# design.net
KiCad netlist of a schematic drawn in EasyEDA
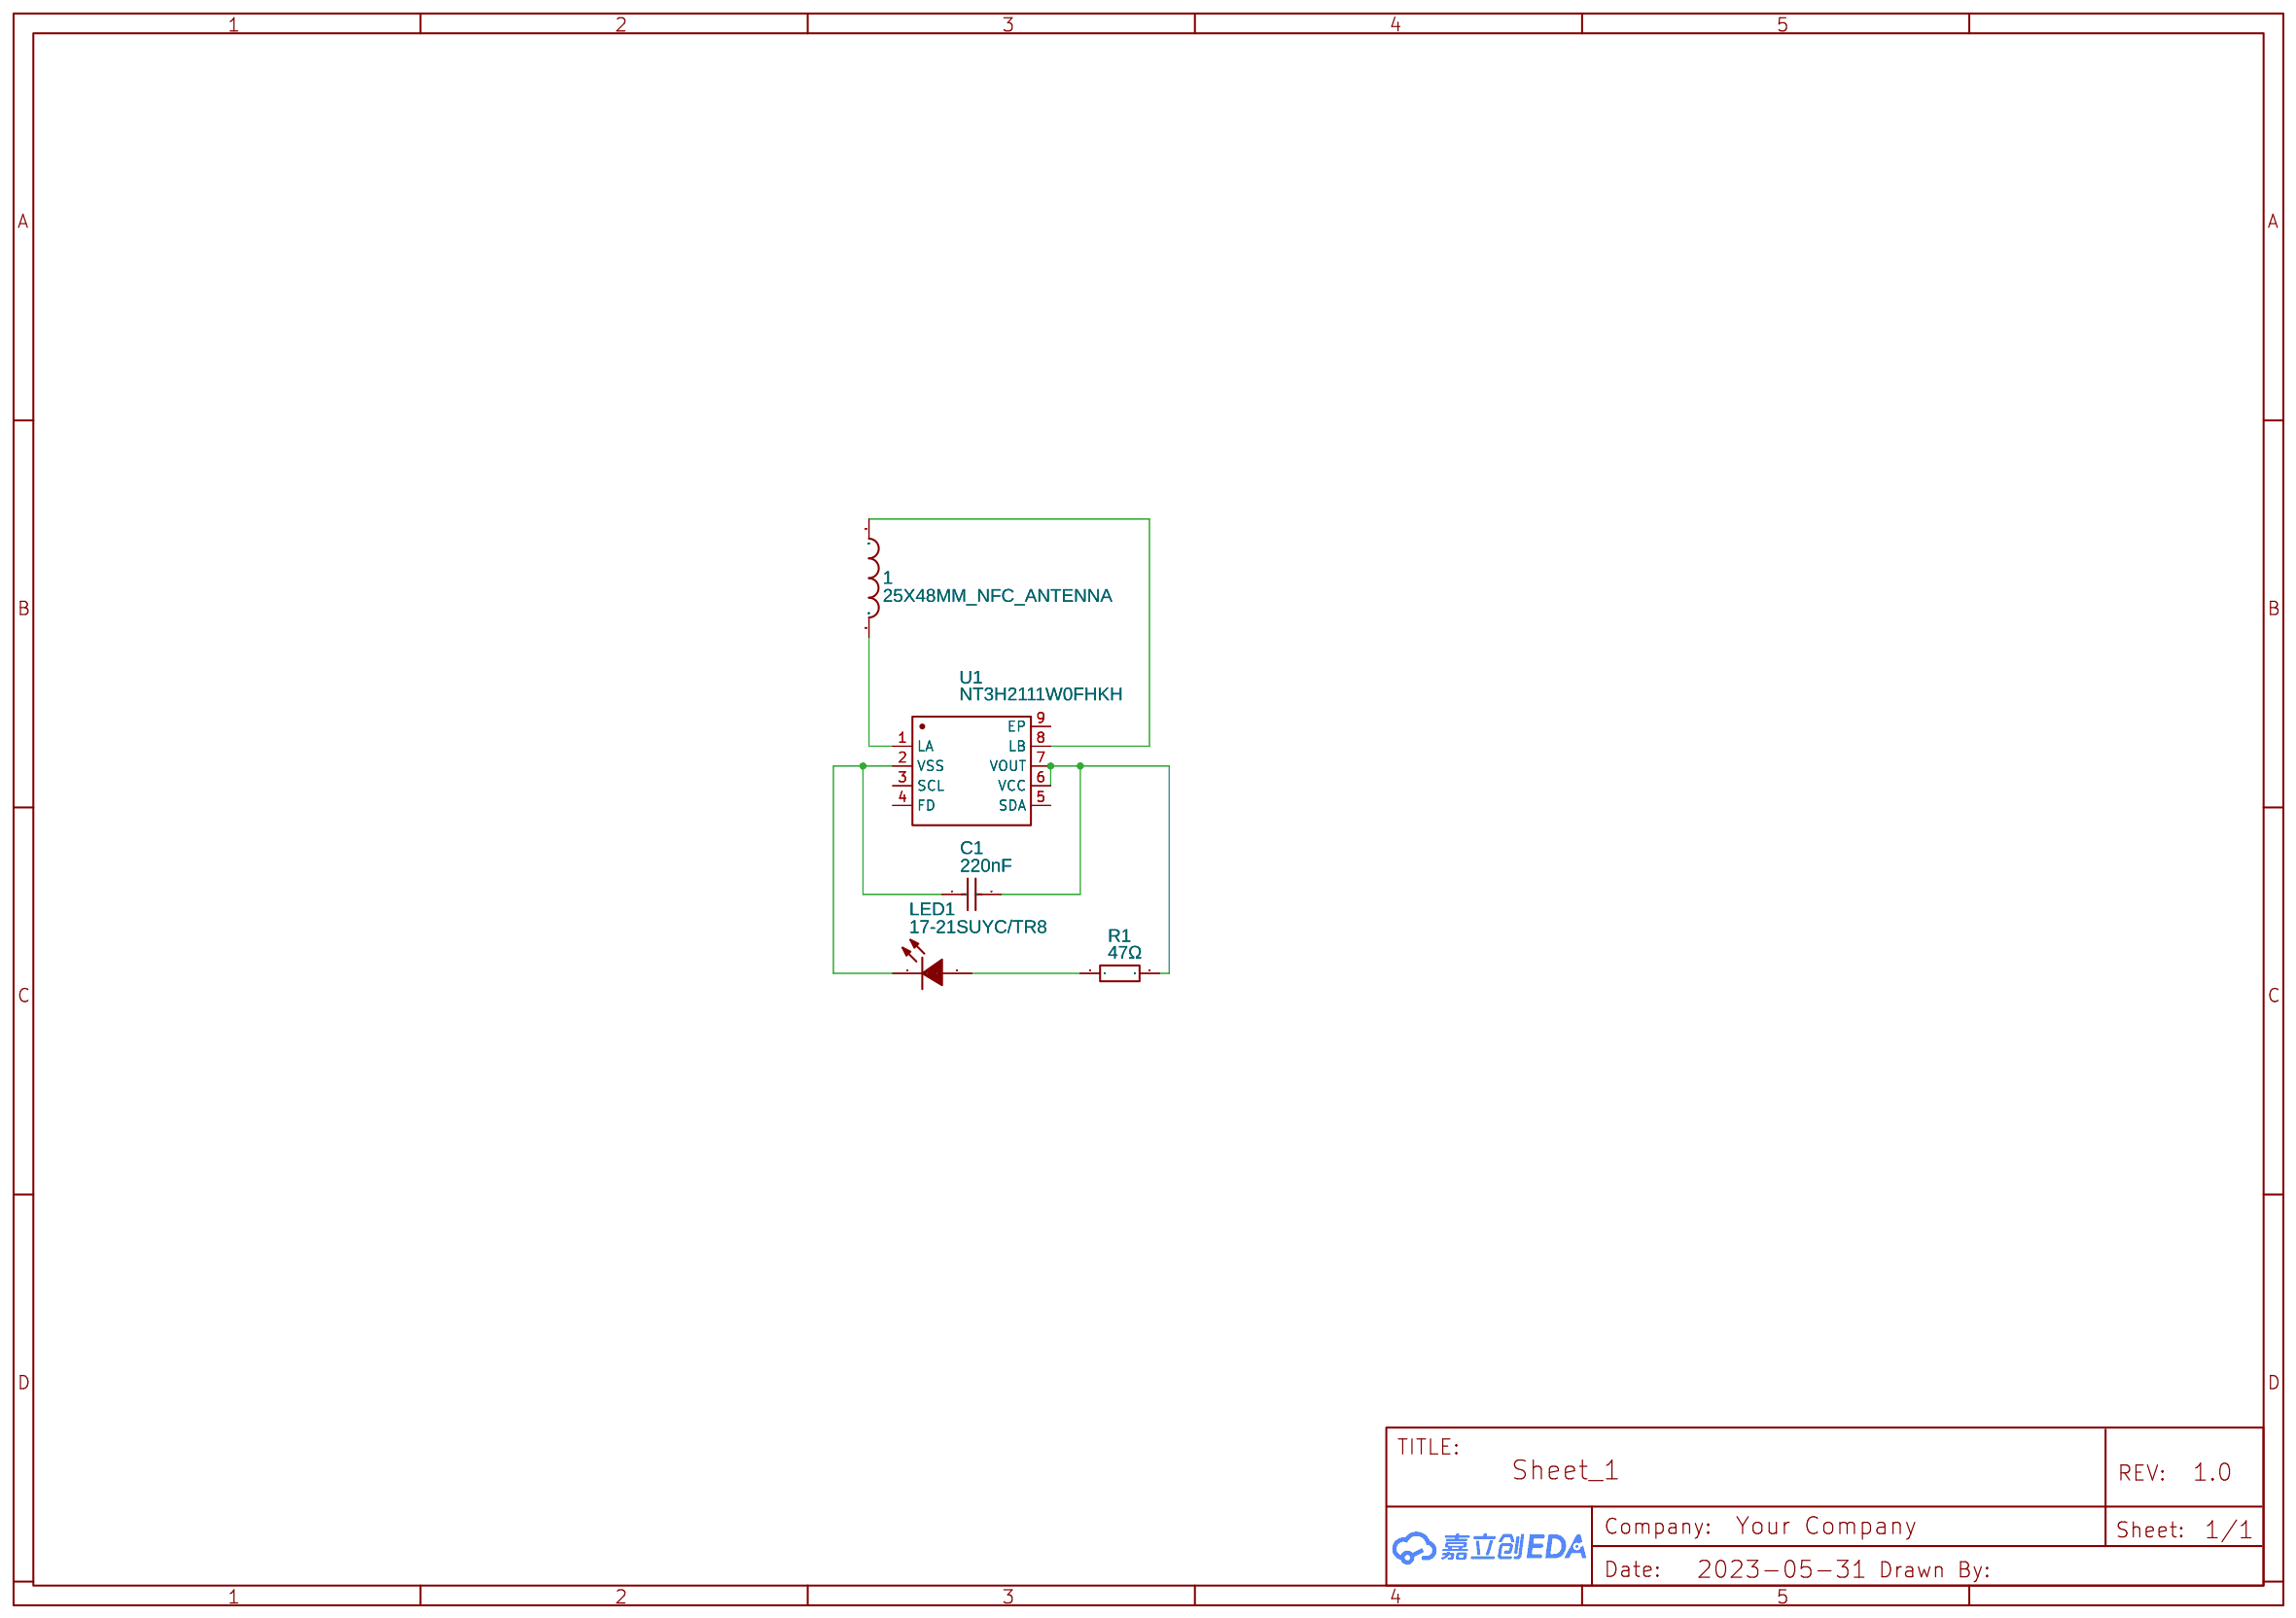
[diagram p0: schematic sheet]

(export (version "E")
  (design (tool "Eeschema 10.0.6"))
  (components
    (comp (ref "1") (value "25X48MM_NFC_ANTENNA") (libsource (lib "") (part "25X48MM_NFC_ANTENNA")))
    (comp (ref "C1")
      (value "220nF")
      (fields
        (field (name "BOM_Manufacturer Part") "CL10B224KA8NNNC")
        (field (name "BOM_Supplier Part") "C21120")
      )
      (libsource (lib "") (part "CL10B224KA8NNNC"))
    )
    (comp (ref "LED1")
      (value "17-21SUYC/TR8")
      (fields (field (name "BOM_Manufacturer Part") "KT-0805黄灯") (field (name "BOM_Supplier Part") "C2296"))
      (libsource (lib "") (part "17-21SUYC/TR8"))
    )
    (comp (ref "R1")
      (value "47Ω")
      (fields
        (field (name "BOM_Manufacturer Part") "0603WAF470JT5E")
        (field (name "BOM_Supplier Part") "C23182")
      )
      (libsource (lib "") (part "0603WAF470JT5E"))
    )
    (comp (ref "U1")
      (value "NT3H2111W0FHKH")
      (fields (field (name "BOM_Supplier Part") "C710403"))
      (libsource (lib "") (part "NT3H2111W0FHKH"))
    )
  )
  (nets
    (net (code "1") (name "Net-(LED1-+)") (class "Default")
      (node (ref "LED1") (pin "1") (pinfunction "+_1") (pintype "unspecified"))
      (node (ref "R1") (pin "1") (pinfunction "1_1") (pintype "input"))
    )
    (net (code "2") (name "Net-(LED1--)") (class "Default")
      (node (ref "C1") (pin "1") (pinfunction "1_1") (pintype "input"))
      (node (ref "LED1") (pin "2") (pinfunction "-_2") (pintype "unspecified"))
      (node (ref "U1") (pin "2") (pinfunction "VSS_2") (pintype "unspecified"))
    )
    (net (code "3") (name "Net-(U1-LA)") (class "Default")
      (node (ref "1") (pin "P$2") (pinfunction "P$2_P$2") (pintype "bidirectional"))
      (node (ref "U1") (pin "1") (pinfunction "LA_1") (pintype "unspecified"))
    )
    (net (code "4") (name "Net-(U1-LB)") (class "Default")
      (node (ref "1") (pin "P$1") (pinfunction "P$1_P$1") (pintype "bidirectional"))
      (node (ref "U1") (pin "8") (pinfunction "LB_8") (pintype "unspecified"))
    )
    (net (code "5") (name "Net-(U1-VCC)") (class "Default")
      (node (ref "C1") (pin "2") (pinfunction "2_2") (pintype "input"))
      (node (ref "R1") (pin "2") (pinfunction "2_2") (pintype "input"))
      (node (ref "U1") (pin "6") (pinfunction "VCC_6") (pintype "unspecified"))
      (node (ref "U1") (pin "7") (pinfunction "VOUT_7") (pintype "unspecified"))
    )
    (net (code "6") (name "unconnected-(U1-EP-Pad9)") (class "Default")
      (node (ref "U1") (pin "9") (pinfunction "EP_9") (pintype "unspecified"))
    )
    (net (code "7") (name "unconnected-(U1-FD-Pad4)") (class "Default")
      (node (ref "U1") (pin "4") (pinfunction "FD_4") (pintype "unspecified"))
    )
    (net (code "8") (name "unconnected-(U1-SCL-Pad3)") (class "Default")
      (node (ref "U1") (pin "3") (pinfunction "SCL_3") (pintype "unspecified"))
    )
    (net (code "9") (name "unconnected-(U1-SDA-Pad5)") (class "Default")
      (node (ref "U1") (pin "5") (pinfunction "SDA_5") (pintype "unspecified"))
    )
  )
)
